# alarm_clock.net
KiCad netlist of a schematic drawn in EAGLE
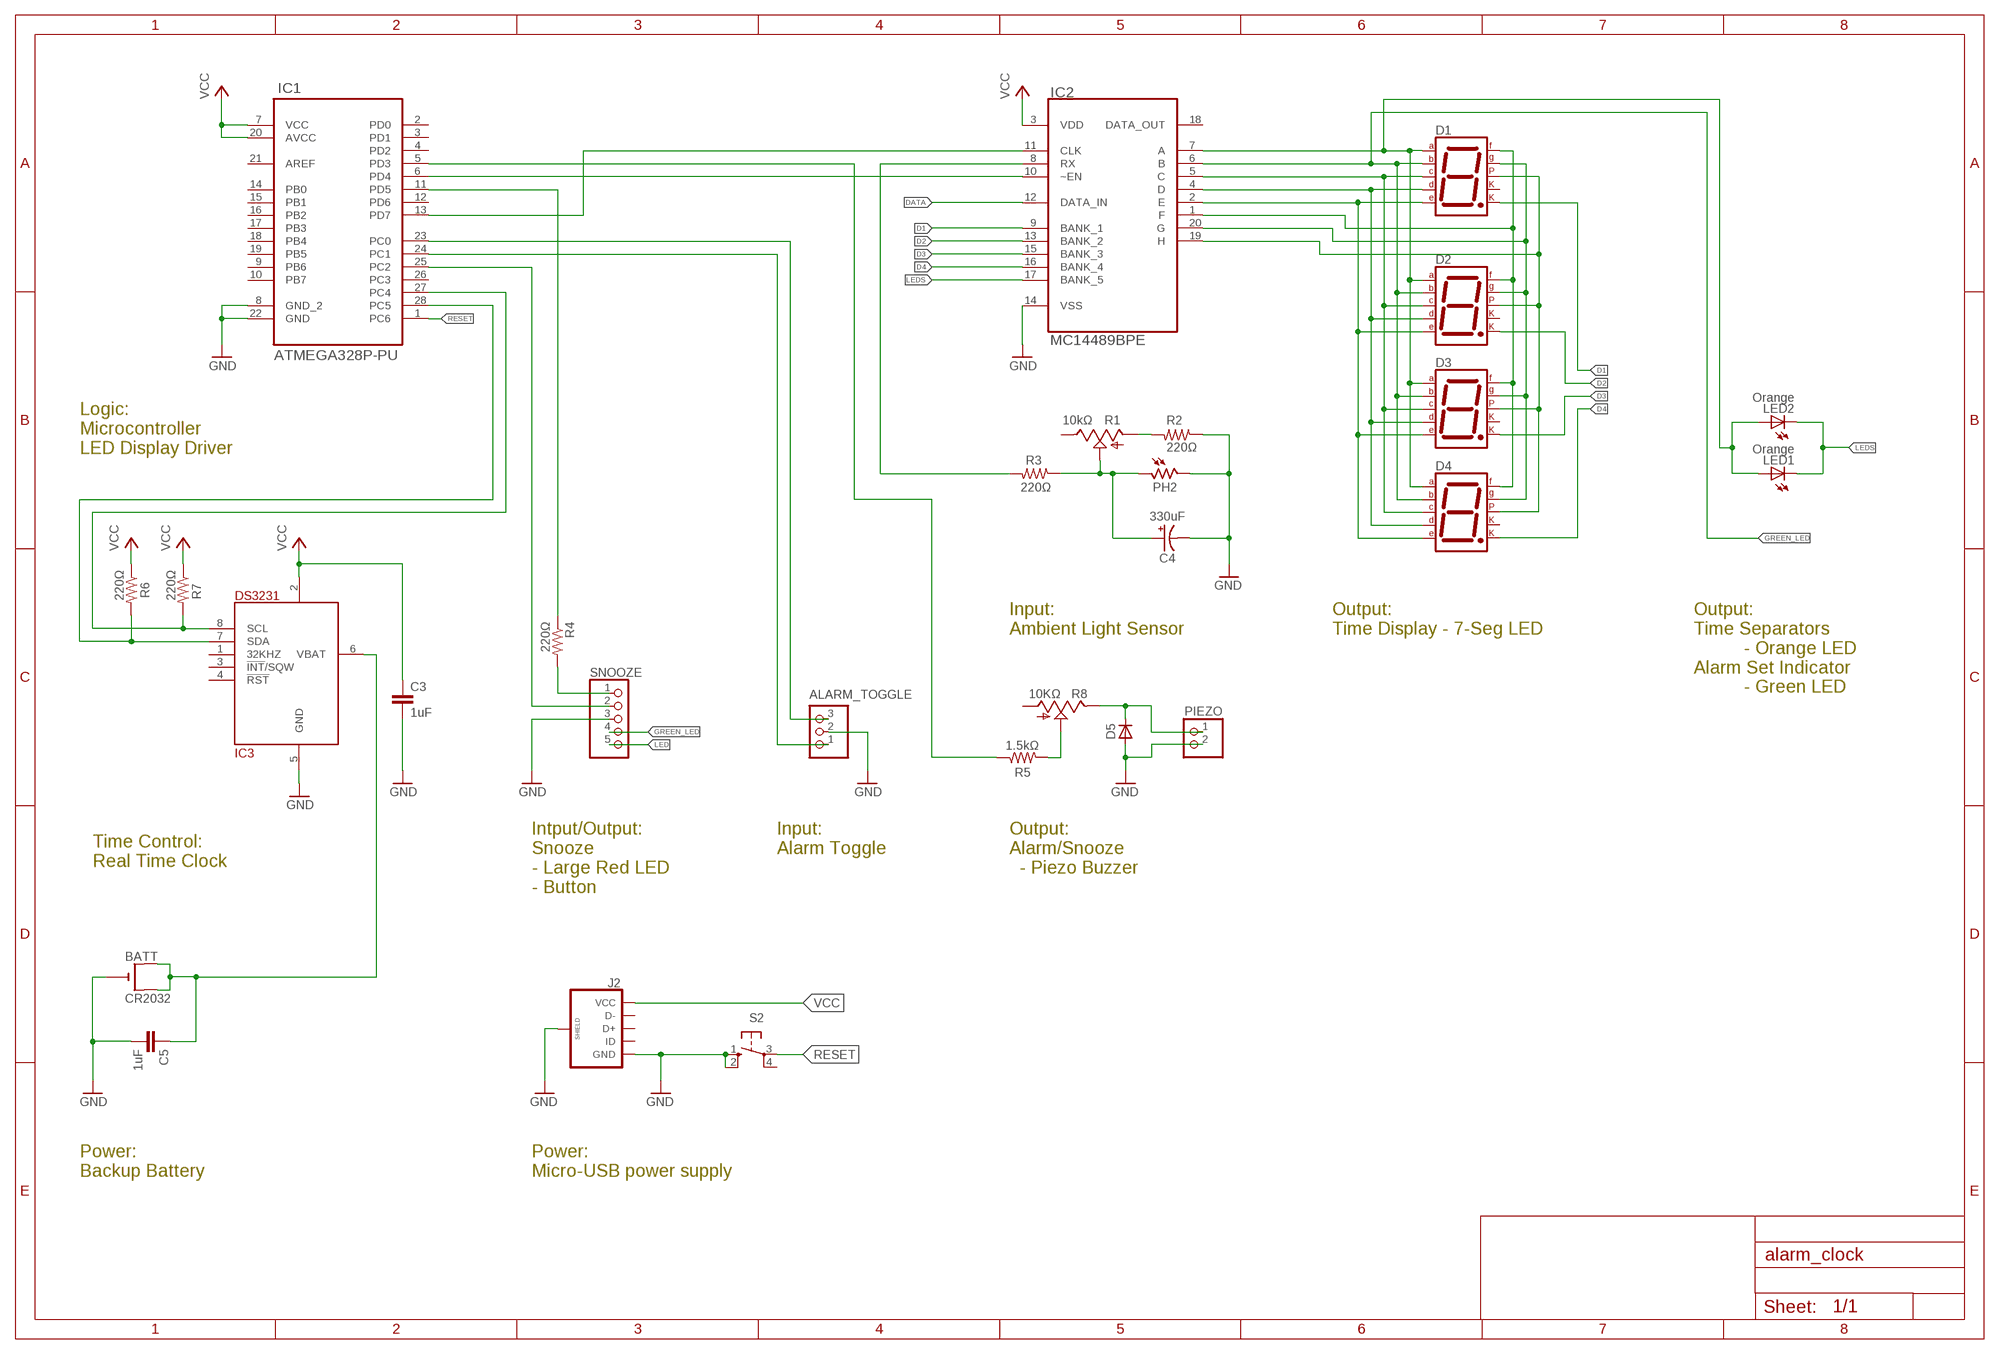
[diagram p0: schematic, sheet 1]

(export (version "E")
  (design (tool "Eeschema 10.0.6"))
  (components
    (comp (ref "ALARM_TOGGLE")
      (value "PINHD-1X3/90")
      (footprint "eagle-import:1X03_90")
      (libsource (lib "eagle-import") (part "PINHD-1X3/90"))
    )
    (comp (ref "BATT")
      (value "CR2032")
      (footprint "eagle-import:CR2032-THRU")
      (fields (field (name "MF") "KEYSTONE") (field (name "MPN") "1066.."))
      (libsource (lib "eagle-import") (part "CR2032THM"))
    )
    (comp (ref "C3")
      (value "1uF")
      (footprint "eagle-import:C025-024X044")
      (libsource (lib "eagle-import") (part "C-EU025-024X044"))
    )
    (comp (ref "C4")
      (value "330uF")
      (footprint "eagle-import:E2,5-6")
      (libsource (lib "eagle-import") (part "CPOL-USE2.5-6"))
    )
    (comp (ref "C5")
      (value "1uF")
      (footprint "eagle-import:C025-024X044")
      (libsource (lib "eagle-import") (part "C-EU025-024X044"))
    )
    (comp (ref "D1")
      (value "7SEG-CK")
      (footprint "eagle-import:7SEG-13")
      (libsource (lib "eagle-import") (part "7SEG-CK"))
    )
    (comp (ref "D2")
      (value "7SEG-CK")
      (footprint "eagle-import:7SEG-13")
      (libsource (lib "eagle-import") (part "7SEG-CK"))
    )
    (comp (ref "D3")
      (value "7SEG-CK")
      (footprint "eagle-import:7SEG-13")
      (libsource (lib "eagle-import") (part "7SEG-CK"))
    )
    (comp (ref "D4")
      (value "7SEG-CK")
      (footprint "eagle-import:7SEG-13")
      (libsource (lib "eagle-import") (part "7SEG-CK"))
    )
    (comp (ref "D5")
      (value "1N4148DO35-7")
      (footprint "eagle-import:DO35-7")
      (libsource (lib "eagle-import") (part "1N4148DO35-7"))
    )
    (comp (ref "IC1")
      (value "ATMEGA328P-PU")
      (footprint "eagle-import:DIP254P762X457-28")
      (fields (field (name "MF") "ATMEL"))
      (libsource (lib "eagle-import") (part "ATMEGA328P-PU"))
    )
    (comp (ref "IC2")
      (value "MC14489BPE")
      (footprint "eagle-import:DIP254P762X457-20")
      (libsource (lib "eagle-import") (part "MC14489BPE"))
    )
    (comp (ref "IC3")
      (value "DS3231")
      (footprint "eagle-import:DS3231-8_SO")
      (libsource (lib "eagle-import") (part "DS3231"))
    )
    (comp (ref "J2")
      (value "USB_MICROB_PLUG-PTH2")
      (footprint "eagle-import:MICRO-B-TH")
      (libsource (lib "eagle-import") (part "USB_MICROB_PLUG-PTH2"))
    )
    (comp (ref "LED1")
      (value "Orange")
      (footprint "eagle-import:LED3MM")
      (fields (field (name "MF") "MULTICOMP") (field (name "MPN") "MCL053HAD/12"))
      (libsource (lib "eagle-import") (part "LED3MM"))
    )
    (comp (ref "LED2")
      (value "Orange")
      (footprint "eagle-import:LED3MM")
      (fields (field (name "MF") "MULTICOMP") (field (name "MPN") "MCL053HAD/12"))
      (libsource (lib "eagle-import") (part "LED3MM"))
    )
    (comp (ref "PH2")
      (value "A1050_09")
      (footprint "eagle-import:T0-46-A10XX")
      (libsource (lib "eagle-import") (part "A1050_09"))
    )
    (comp (ref "PIEZO")
      (value "PINHD-1X2/90")
      (footprint "eagle-import:1X02_90")
      (libsource (lib "eagle-import") (part "PINHD-1X2/90"))
    )
    (comp (ref "R1")
      (value "10kΩ")
      (footprint "eagle-import:CA6V")
      (libsource (lib "eagle-import") (part "TRIM_US-CA6V"))
    )
    (comp (ref "R2")
      (value "220Ω")
      (footprint "eagle-import:0207_7")
      (libsource (lib "eagle-import") (part "R-US_0207/7"))
    )
    (comp (ref "R3")
      (value "220Ω")
      (footprint "eagle-import:0207_7")
      (libsource (lib "eagle-import") (part "R-US_0207/7"))
    )
    (comp (ref "R4")
      (value "220Ω")
      (footprint "eagle-import:0207_7")
      (libsource (lib "eagle-import") (part "R-US_0207/7"))
    )
    (comp (ref "R5")
      (value "1.5kΩ")
      (footprint "eagle-import:0207_7")
      (libsource (lib "eagle-import") (part "R-US_0207/7"))
    )
    (comp (ref "R6")
      (value "220Ω")
      (footprint "eagle-import:0207_7")
      (libsource (lib "eagle-import") (part "R-US_0207/7"))
    )
    (comp (ref "R7")
      (value "220Ω")
      (footprint "eagle-import:0207_7")
      (libsource (lib "eagle-import") (part "R-US_0207/7"))
    )
    (comp (ref "R8")
      (value "10KΩ")
      (footprint "eagle-import:CA6V")
      (libsource (lib "eagle-import") (part "TRIM_US-CA6V"))
    )
    (comp (ref "S2")
      (value "10-XX")
      (footprint "eagle-import:B3F-10XX")
      (fields (field (name "MPN") "B3F-1000"))
      (libsource (lib "eagle-import") (part "10-XX"))
    )
    (comp (ref "SNOOZE")
      (value "PINHD-1X5/90")
      (footprint "eagle-import:1X05_90")
      (libsource (lib "eagle-import") (part "PINHD-1X5/90"))
    )
  )
  (nets
    (net (code "1") (name "D1") (class "Default")
      (node (ref "D1") (pin "8") (pinfunction "CK2_8") (pintype "passive"))
      (node (ref "IC2") (pin "9") (pinfunction "BANK_1_9") (pintype "input"))
    )
    (net (code "2") (name "D2") (class "Default")
      (node (ref "D2") (pin "8") (pinfunction "CK2_8") (pintype "passive"))
      (node (ref "IC2") (pin "13") (pinfunction "BANK_2_13") (pintype "input"))
    )
    (net (code "3") (name "D3") (class "Default")
      (node (ref "D3") (pin "8") (pinfunction "CK2_8") (pintype "passive"))
      (node (ref "IC2") (pin "15") (pinfunction "BANK_3_15") (pintype "input"))
    )
    (net (code "4") (name "D4") (class "Default")
      (node (ref "D4") (pin "8") (pinfunction "CK2_8") (pintype "passive"))
      (node (ref "IC2") (pin "16") (pinfunction "BANK_4_16") (pintype "input"))
    )
    (net (code "5") (name "DATA") (class "Default")
      (node (ref "IC2") (pin "12") (pinfunction "DATA_IN_12") (pintype "input"))
    )
    (net (code "6") (name "GND") (class "Default")
      (node (ref "ALARM_TOGGLE") (pin "2") (pinfunction "2_2") (pintype "passive"))
      (node (ref "BATT") (pin "-") (pinfunction "-_-") (pintype "passive"))
      (node (ref "C3") (pin "2") (pinfunction "2_2") (pintype "passive"))
      (node (ref "C4") (pin "-") (pinfunction "-_-") (pintype "passive"))
      (node (ref "C5") (pin "2") (pinfunction "2_2") (pintype "passive"))
      (node (ref "D5") (pin "A") (pinfunction "A_A") (pintype "passive"))
      (node (ref "IC1") (pin "22") (pinfunction "GND_22") (pintype "passive"))
      (node (ref "IC1") (pin "8") (pinfunction "GND_2_8") (pintype "passive"))
      (node (ref "IC2") (pin "14") (pinfunction "VSS_14") (pintype "power_in"))
      (node (ref "IC3") (pin "5") (pinfunction "GND_5") (pintype "bidirectional"))
      (node (ref "J2") (pin "5") (pinfunction "GND_5") (pintype "bidirectional"))
      (node (ref "J2") (pin "P$1") (pinfunction "SHIELD_P$1") (pintype "bidirectional"))
      (node (ref "PH2") (pin "2") (pinfunction "2_2") (pintype "passive"))
      (node (ref "PIEZO") (pin "2") (pinfunction "2_2") (pintype "passive"))
      (node (ref "R2") (pin "1") (pinfunction "1_1") (pintype "passive"))
      (node (ref "S2") (pin "1") (pinfunction "S_1") (pintype "passive"))
      (node (ref "S2") (pin "2") (pinfunction "S1_2") (pintype "passive"))
      (node (ref "SNOOZE") (pin "3") (pinfunction "3_3") (pintype "passive"))
    )
    (net (code "7") (name "GREEN_LED") (class "Default")
      (node (ref "D1") (pin "6") (pinfunction "B_6") (pintype "passive"))
      (node (ref "D2") (pin "6") (pinfunction "B_6") (pintype "passive"))
      (node (ref "D3") (pin "6") (pinfunction "B_6") (pintype "passive"))
      (node (ref "D4") (pin "6") (pinfunction "B_6") (pintype "passive"))
      (node (ref "IC2") (pin "6") (pinfunction "B_6") (pintype "output"))
      (node (ref "SNOOZE") (pin "4") (pinfunction "4_4") (pintype "passive"))
    )
    (net (code "8") (name "LED") (class "Default")
      (node (ref "SNOOZE") (pin "5") (pinfunction "5_5") (pintype "passive"))
    )
    (net (code "9") (name "LEDS") (class "Default")
      (node (ref "IC2") (pin "17") (pinfunction "BANK_5_17") (pintype "input"))
      (node (ref "LED1") (pin "K") (pinfunction "C_K") (pintype "passive"))
      (node (ref "LED2") (pin "K") (pinfunction "C_K") (pintype "passive"))
    )
    (net (code "10") (name "Net-(BATT-+)") (class "Default")
      (node (ref "BATT") (pin "+1") (pinfunction "+_+1") (pintype "passive"))
      (node (ref "BATT") (pin "+2") (pinfunction "+1_+2") (pintype "passive"))
      (node (ref "C5") (pin "1") (pinfunction "1_1") (pintype "passive"))
      (node (ref "IC3") (pin "6") (pinfunction "VBAT_6") (pintype "bidirectional"))
    )
    (net (code "11") (name "Net-(C4-Pad+)") (class "Default")
      (node (ref "C4") (pin "+") (pinfunction "+_+") (pintype "passive"))
      (node (ref "PH2") (pin "1") (pinfunction "1_1") (pintype "passive"))
      (node (ref "R1") (pin "S") (pinfunction "S_S") (pintype "passive"))
      (node (ref "R3") (pin "1") (pinfunction "1_1") (pintype "passive"))
    )
    (net (code "12") (name "Net-(D1-A)") (class "Default")
      (node (ref "D1") (pin "7") (pinfunction "A_7") (pintype "passive"))
      (node (ref "D2") (pin "7") (pinfunction "A_7") (pintype "passive"))
      (node (ref "D3") (pin "7") (pinfunction "A_7") (pintype "passive"))
      (node (ref "D4") (pin "7") (pinfunction "A_7") (pintype "passive"))
      (node (ref "IC2") (pin "7") (pinfunction "A_7") (pintype "output"))
      (node (ref "LED1") (pin "A") (pinfunction "A_A") (pintype "passive"))
      (node (ref "LED2") (pin "A") (pinfunction "A_A") (pintype "passive"))
    )
    (net (code "13") (name "Net-(D1-C)") (class "Default")
      (node (ref "D1") (pin "4") (pinfunction "C_4") (pintype "passive"))
      (node (ref "D2") (pin "4") (pinfunction "C_4") (pintype "passive"))
      (node (ref "D3") (pin "4") (pinfunction "C_4") (pintype "passive"))
      (node (ref "D4") (pin "4") (pinfunction "C_4") (pintype "passive"))
      (node (ref "IC2") (pin "5") (pinfunction "C_5") (pintype "output"))
    )
    (net (code "14") (name "Net-(D1-D)") (class "Default")
      (node (ref "D1") (pin "2") (pinfunction "D_2") (pintype "passive"))
      (node (ref "D2") (pin "2") (pinfunction "D_2") (pintype "passive"))
      (node (ref "D3") (pin "2") (pinfunction "D_2") (pintype "passive"))
      (node (ref "D4") (pin "2") (pinfunction "D_2") (pintype "passive"))
      (node (ref "IC2") (pin "4") (pinfunction "D_4") (pintype "output"))
    )
    (net (code "15") (name "Net-(D1-DP)") (class "Default")
      (node (ref "D1") (pin "5") (pinfunction "DP_5") (pintype "passive"))
      (node (ref "D2") (pin "5") (pinfunction "DP_5") (pintype "passive"))
      (node (ref "D3") (pin "5") (pinfunction "DP_5") (pintype "passive"))
      (node (ref "D4") (pin "5") (pinfunction "DP_5") (pintype "passive"))
      (node (ref "IC2") (pin "19") (pinfunction "H_19") (pintype "output"))
    )
    (net (code "16") (name "Net-(D1-E)") (class "Default")
      (node (ref "D1") (pin "1") (pinfunction "E_1") (pintype "passive"))
      (node (ref "D2") (pin "1") (pinfunction "E_1") (pintype "passive"))
      (node (ref "D3") (pin "1") (pinfunction "E_1") (pintype "passive"))
      (node (ref "D4") (pin "1") (pinfunction "E_1") (pintype "passive"))
      (node (ref "IC2") (pin "2") (pinfunction "E_2") (pintype "output"))
    )
    (net (code "17") (name "Net-(D1-F)") (class "Default")
      (node (ref "D1") (pin "9") (pinfunction "F_9") (pintype "passive"))
      (node (ref "D2") (pin "9") (pinfunction "F_9") (pintype "passive"))
      (node (ref "D3") (pin "9") (pinfunction "F_9") (pintype "passive"))
      (node (ref "D4") (pin "9") (pinfunction "F_9") (pintype "passive"))
      (node (ref "IC2") (pin "1") (pinfunction "F_1") (pintype "output"))
    )
    (net (code "18") (name "Net-(D1-G)") (class "Default")
      (node (ref "D1") (pin "10") (pinfunction "G_10") (pintype "passive"))
      (node (ref "D2") (pin "10") (pinfunction "G_10") (pintype "passive"))
      (node (ref "D3") (pin "10") (pinfunction "G_10") (pintype "passive"))
      (node (ref "D4") (pin "10") (pinfunction "G_10") (pintype "passive"))
      (node (ref "IC2") (pin "20") (pinfunction "G_20") (pintype "output"))
    )
    (net (code "19") (name "Net-(D5-PadC)") (class "Default")
      (node (ref "D5") (pin "C") (pinfunction "C_C") (pintype "passive"))
      (node (ref "PIEZO") (pin "1") (pinfunction "1_1") (pintype "passive"))
      (node (ref "R8") (pin "E") (pinfunction "E_E") (pintype "passive"))
    )
    (net (code "20") (name "Net-(IC1-PC0)") (class "Default")
      (node (ref "ALARM_TOGGLE") (pin "3") (pinfunction "3_3") (pintype "passive"))
      (node (ref "IC1") (pin "23") (pinfunction "PC0_23") (pintype "bidirectional"))
    )
    (net (code "21") (name "Net-(IC1-PC1)") (class "Default")
      (node (ref "ALARM_TOGGLE") (pin "1") (pinfunction "1_1") (pintype "passive"))
      (node (ref "IC1") (pin "24") (pinfunction "PC1_24") (pintype "bidirectional"))
    )
    (net (code "22") (name "Net-(IC1-PC2)") (class "Default")
      (node (ref "IC1") (pin "25") (pinfunction "PC2_25") (pintype "bidirectional"))
      (node (ref "SNOOZE") (pin "2") (pinfunction "2_2") (pintype "passive"))
    )
    (net (code "23") (name "Net-(IC1-PC4)") (class "Default")
      (node (ref "IC1") (pin "27") (pinfunction "PC4_27") (pintype "bidirectional"))
      (node (ref "IC3") (pin "8") (pinfunction "SCL_8") (pintype "bidirectional"))
      (node (ref "R7") (pin "2") (pinfunction "2_2") (pintype "passive"))
    )
    (net (code "24") (name "Net-(IC1-PC5)") (class "Default")
      (node (ref "IC1") (pin "28") (pinfunction "PC5_28") (pintype "bidirectional"))
      (node (ref "IC3") (pin "7") (pinfunction "SDA_7") (pintype "bidirectional"))
      (node (ref "R6") (pin "2") (pinfunction "2_2") (pintype "passive"))
    )
    (net (code "25") (name "Net-(IC1-PD3)") (class "Default")
      (node (ref "IC1") (pin "5") (pinfunction "PD3_5") (pintype "bidirectional"))
      (node (ref "R5") (pin "1") (pinfunction "1_1") (pintype "passive"))
    )
    (net (code "26") (name "Net-(IC1-PD4)") (class "Default")
      (node (ref "IC1") (pin "6") (pinfunction "PD4_6") (pintype "bidirectional"))
      (node (ref "IC2") (pin "10") (pinfunction "~{EN}_10") (pintype "input"))
    )
    (net (code "27") (name "Net-(IC1-PD5)") (class "Default")
      (node (ref "IC1") (pin "11") (pinfunction "PD5_11") (pintype "bidirectional"))
      (node (ref "R4") (pin "1") (pinfunction "1_1") (pintype "passive"))
    )
    (net (code "28") (name "Net-(IC1-PD7)") (class "Default")
      (node (ref "IC1") (pin "13") (pinfunction "PD7_13") (pintype "bidirectional"))
      (node (ref "IC2") (pin "11") (pinfunction "CLK_11") (pintype "input"))
    )
    (net (code "29") (name "Net-(IC2-RX)") (class "Default")
      (node (ref "IC2") (pin "8") (pinfunction "RX_8") (pintype "passive"))
      (node (ref "R3") (pin "2") (pinfunction "2_2") (pintype "passive"))
    )
    (net (code "30") (name "Net-(R1-PadA)") (class "Default")
      (node (ref "R1") (pin "A") (pinfunction "A_A") (pintype "passive"))
      (node (ref "R2") (pin "2") (pinfunction "2_2") (pintype "passive"))
    )
    (net (code "31") (name "Net-(R4-Pad2)") (class "Default")
      (node (ref "R4") (pin "2") (pinfunction "2_2") (pintype "passive"))
      (node (ref "SNOOZE") (pin "1") (pinfunction "1_1") (pintype "passive"))
    )
    (net (code "32") (name "Net-(R5-Pad2)") (class "Default")
      (node (ref "R5") (pin "2") (pinfunction "2_2") (pintype "passive"))
      (node (ref "R8") (pin "S") (pinfunction "S_S") (pintype "passive"))
    )
    (net (code "33") (name "RESET") (class "Default")
      (node (ref "IC1") (pin "1") (pinfunction "PC6_1") (pintype "bidirectional"))
      (node (ref "S2") (pin "3") (pinfunction "P_3") (pintype "passive"))
    )
    (net (code "34") (name "VCC") (class "Default")
      (node (ref "C3") (pin "1") (pinfunction "1_1") (pintype "passive"))
      (node (ref "IC1") (pin "20") (pinfunction "AVCC_20") (pintype "power_in"))
      (node (ref "IC1") (pin "7") (pinfunction "VCC_7") (pintype "power_in"))
      (node (ref "IC2") (pin "3") (pinfunction "VDD_3") (pintype "power_in"))
      (node (ref "IC3") (pin "2") (pinfunction "VCC_2") (pintype "bidirectional"))
      (node (ref "J2") (pin "1") (pinfunction "VCC_1") (pintype "bidirectional"))
      (node (ref "R6") (pin "1") (pinfunction "1_1") (pintype "passive"))
      (node (ref "R7") (pin "1") (pinfunction "1_1") (pintype "passive"))
    )
    (net (code "35") (name "unconnected-(D1-CK1-Pad3)") (class "Default")
      (node (ref "D1") (pin "3") (pinfunction "CK1_3") (pintype "passive"))
    )
    (net (code "36") (name "unconnected-(D2-CK1-Pad3)") (class "Default")
      (node (ref "D2") (pin "3") (pinfunction "CK1_3") (pintype "passive"))
    )
    (net (code "37") (name "unconnected-(D3-CK1-Pad3)") (class "Default")
      (node (ref "D3") (pin "3") (pinfunction "CK1_3") (pintype "passive"))
    )
    (net (code "38") (name "unconnected-(D4-CK1-Pad3)") (class "Default")
      (node (ref "D4") (pin "3") (pinfunction "CK1_3") (pintype "passive"))
    )
    (net (code "39") (name "unconnected-(IC1-AREF-Pad21)") (class "Default")
      (node (ref "IC1") (pin "21") (pinfunction "AREF_21") (pintype "input"))
    )
    (net (code "40") (name "unconnected-(IC1-PB0-Pad14)") (class "Default")
      (node (ref "IC1") (pin "14") (pinfunction "PB0_14") (pintype "bidirectional"))
    )
    (net (code "41") (name "unconnected-(IC1-PB1-Pad15)") (class "Default")
      (node (ref "IC1") (pin "15") (pinfunction "PB1_15") (pintype "bidirectional"))
    )
    (net (code "42") (name "unconnected-(IC1-PB2-Pad16)") (class "Default")
      (node (ref "IC1") (pin "16") (pinfunction "PB2_16") (pintype "bidirectional"))
    )
    (net (code "43") (name "unconnected-(IC1-PB3-Pad17)") (class "Default")
      (node (ref "IC1") (pin "17") (pinfunction "PB3_17") (pintype "bidirectional"))
    )
    (net (code "44") (name "unconnected-(IC1-PB4-Pad18)") (class "Default")
      (node (ref "IC1") (pin "18") (pinfunction "PB4_18") (pintype "bidirectional"))
    )
    (net (code "45") (name "unconnected-(IC1-PB5-Pad19)") (class "Default")
      (node (ref "IC1") (pin "19") (pinfunction "PB5_19") (pintype "bidirectional"))
    )
    (net (code "46") (name "unconnected-(IC1-PB6-Pad9)") (class "Default")
      (node (ref "IC1") (pin "9") (pinfunction "PB6_9") (pintype "bidirectional"))
    )
    (net (code "47") (name "unconnected-(IC1-PB7-Pad10)") (class "Default")
      (node (ref "IC1") (pin "10") (pinfunction "PB7_10") (pintype "bidirectional"))
    )
    (net (code "48") (name "unconnected-(IC1-PC3-Pad26)") (class "Default")
      (node (ref "IC1") (pin "26") (pinfunction "PC3_26") (pintype "bidirectional"))
    )
    (net (code "49") (name "unconnected-(IC1-PD0-Pad2)") (class "Default")
      (node (ref "IC1") (pin "2") (pinfunction "PD0_2") (pintype "bidirectional"))
    )
    (net (code "50") (name "unconnected-(IC1-PD1-Pad3)") (class "Default")
      (node (ref "IC1") (pin "3") (pinfunction "PD1_3") (pintype "bidirectional"))
    )
    (net (code "51") (name "unconnected-(IC1-PD2-Pad4)") (class "Default")
      (node (ref "IC1") (pin "4") (pinfunction "PD2_4") (pintype "bidirectional"))
    )
    (net (code "52") (name "unconnected-(IC1-PD6-Pad12)") (class "Default")
      (node (ref "IC1") (pin "12") (pinfunction "PD6_12") (pintype "bidirectional"))
    )
    (net (code "53") (name "unconnected-(IC2-DATA_OUT-Pad18)") (class "Default")
      (node (ref "IC2") (pin "18") (pinfunction "DATA_OUT_18") (pintype "output"))
    )
    (net (code "54") (name "unconnected-(IC3-32KHZ-Pad1)") (class "Default")
      (node (ref "IC3") (pin "1") (pinfunction "32KHZ_1") (pintype "bidirectional"))
    )
    (net (code "55") (name "unconnected-(IC3-~{INT}{slash}SQW-Pad3)") (class "Default")
      (node (ref "IC3") (pin "3") (pinfunction "~{INT}/SQW_3") (pintype "bidirectional"))
    )
    (net (code "56") (name "unconnected-(IC3-~{RST}-Pad4)") (class "Default")
      (node (ref "IC3") (pin "4") (pinfunction "~{RST}_4") (pintype "bidirectional"))
    )
    (net (code "57") (name "unconnected-(J2-D+-Pad3)") (class "Default")
      (node (ref "J2") (pin "3") (pinfunction "D+_3") (pintype "bidirectional"))
    )
    (net (code "58") (name "unconnected-(J2-D--Pad2)") (class "Default")
      (node (ref "J2") (pin "2") (pinfunction "D-_2") (pintype "bidirectional"))
    )
    (net (code "59") (name "unconnected-(J2-ID-Pad4)") (class "Default")
      (node (ref "J2") (pin "4") (pinfunction "ID_4") (pintype "bidirectional"))
    )
    (net (code "60") (name "unconnected-(R1-PadE)") (class "Default")
      (node (ref "R1") (pin "E") (pinfunction "E_E") (pintype "passive"))
    )
    (net (code "61") (name "unconnected-(R8-PadA)") (class "Default")
      (node (ref "R8") (pin "A") (pinfunction "A_A") (pintype "passive"))
    )
    (net (code "62") (name "unconnected-(S2-P1-Pad4)") (class "Default")
      (node (ref "S2") (pin "4") (pinfunction "P1_4") (pintype "passive"))
    )
  )
)
